# 28ChFNIRS.net
KiCad netlist of a schematic drawn in EAGLE
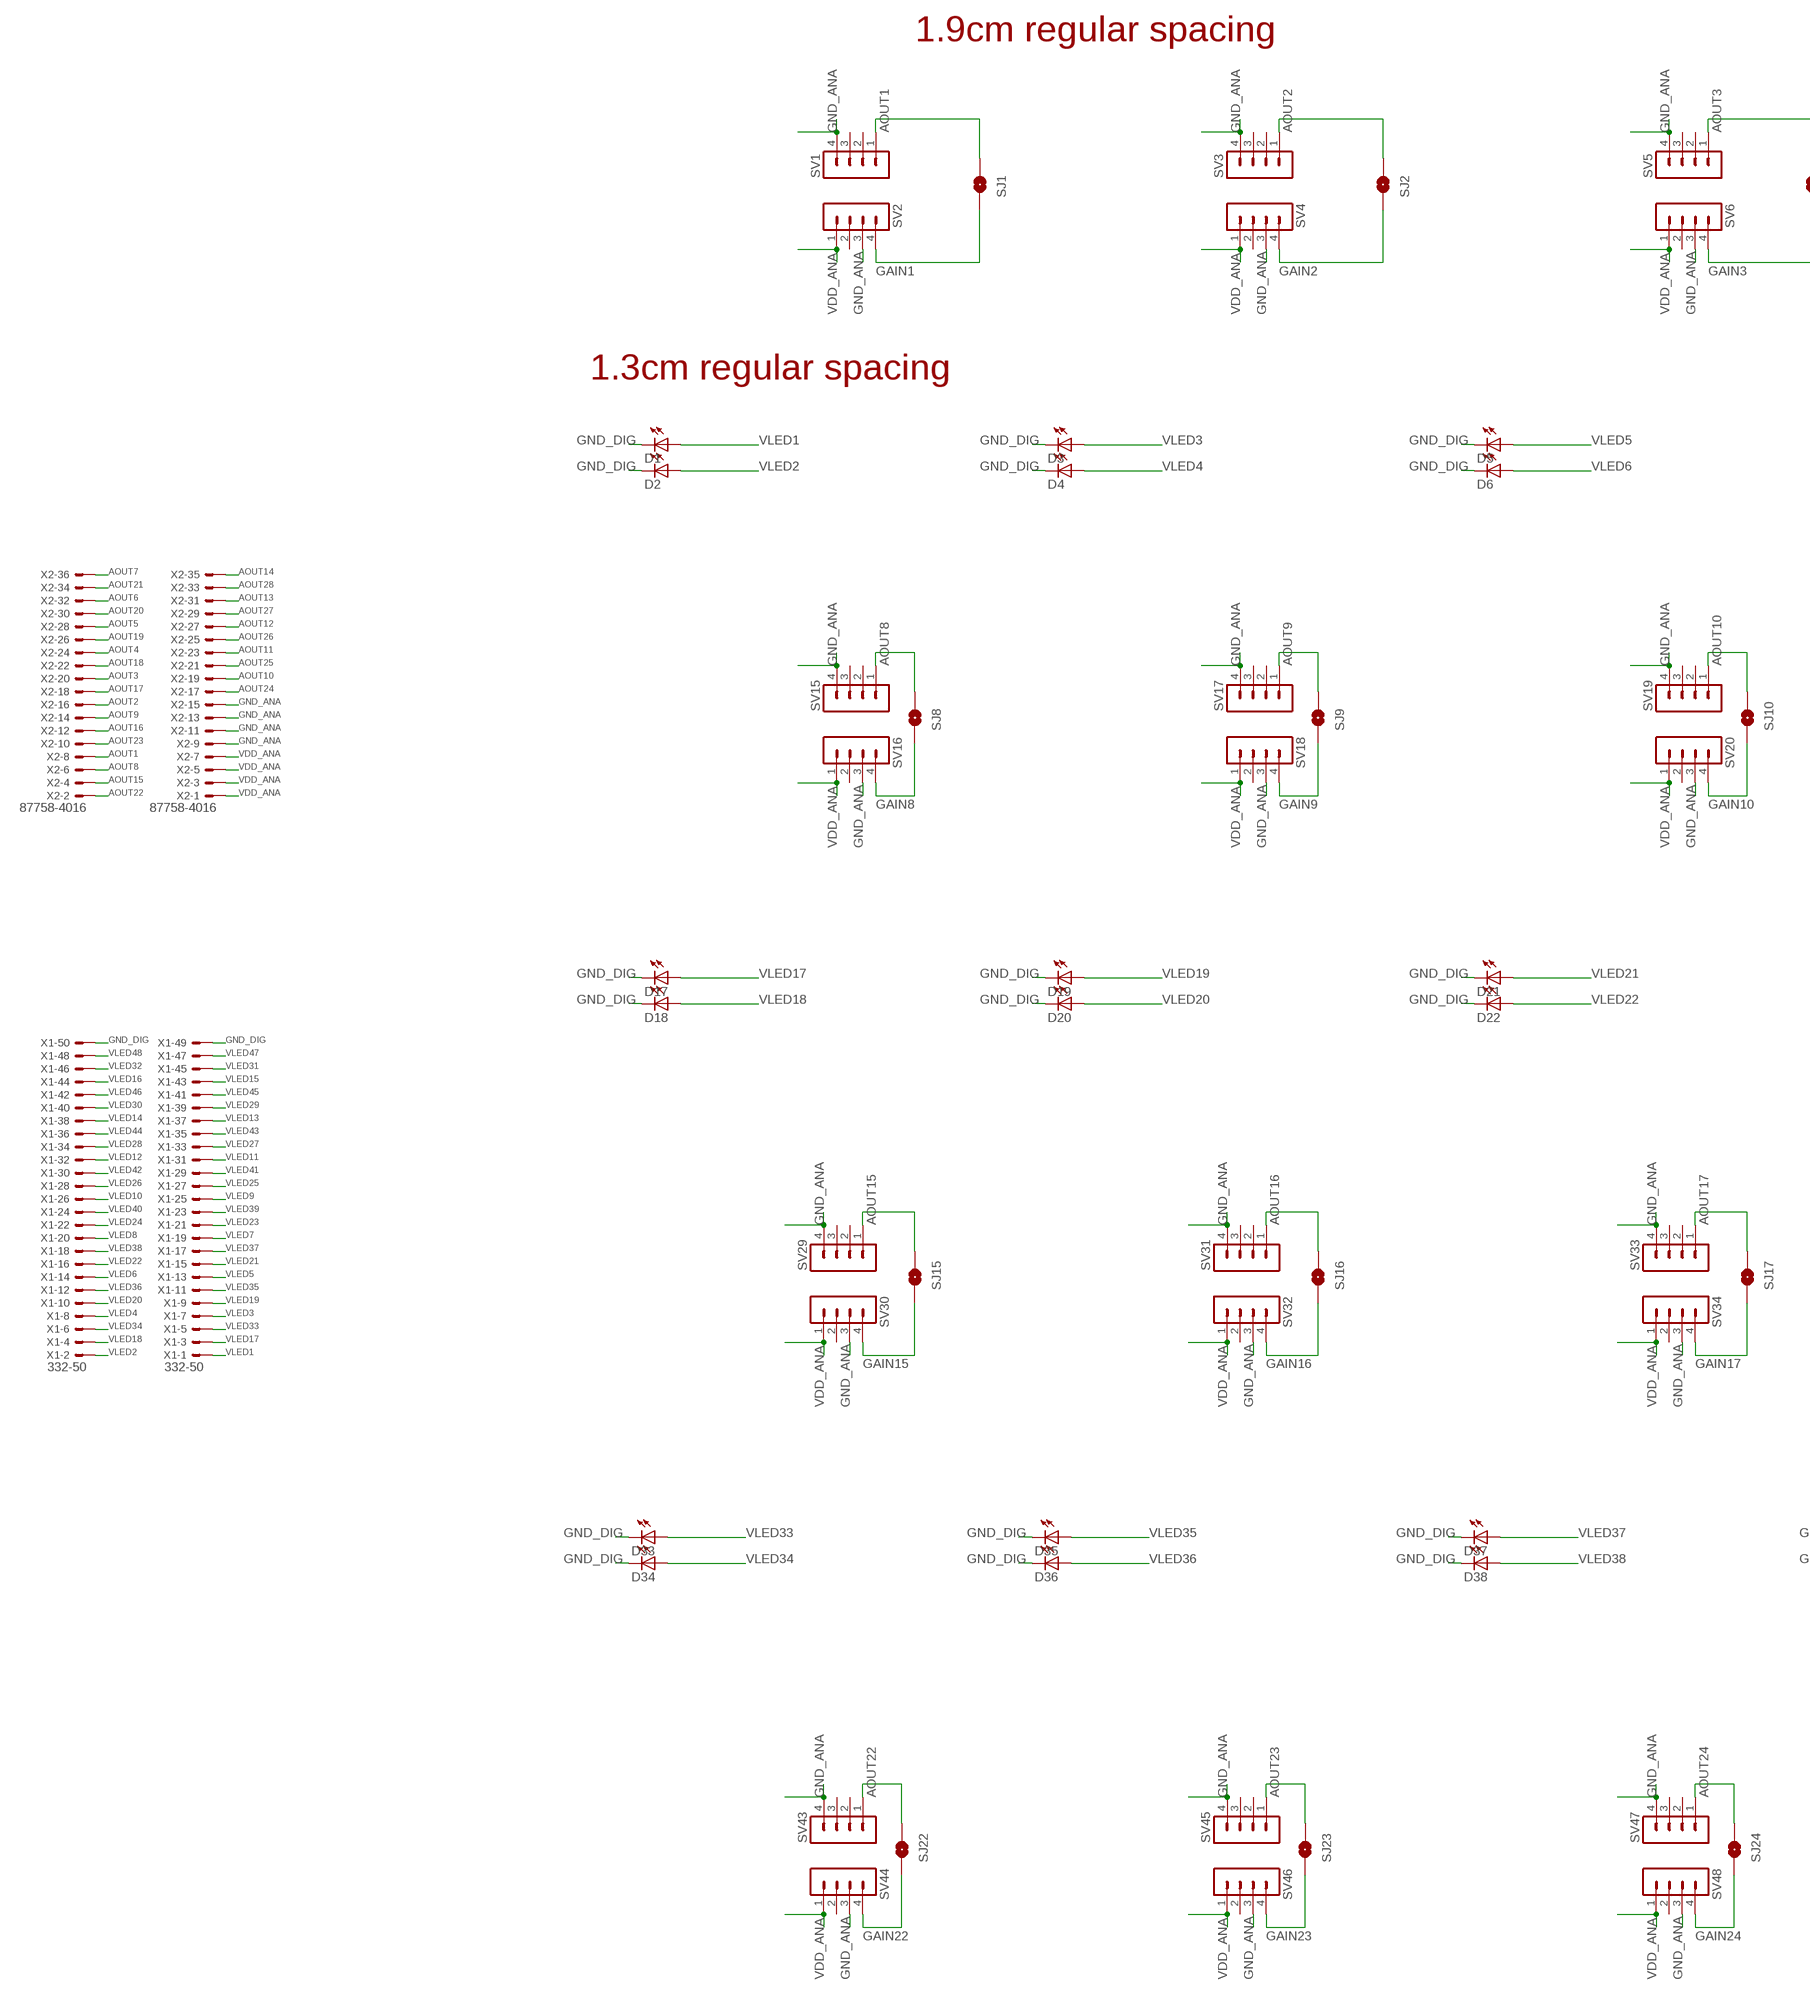
[diagram p0: schematic, sheet 1, part 1 of 2]
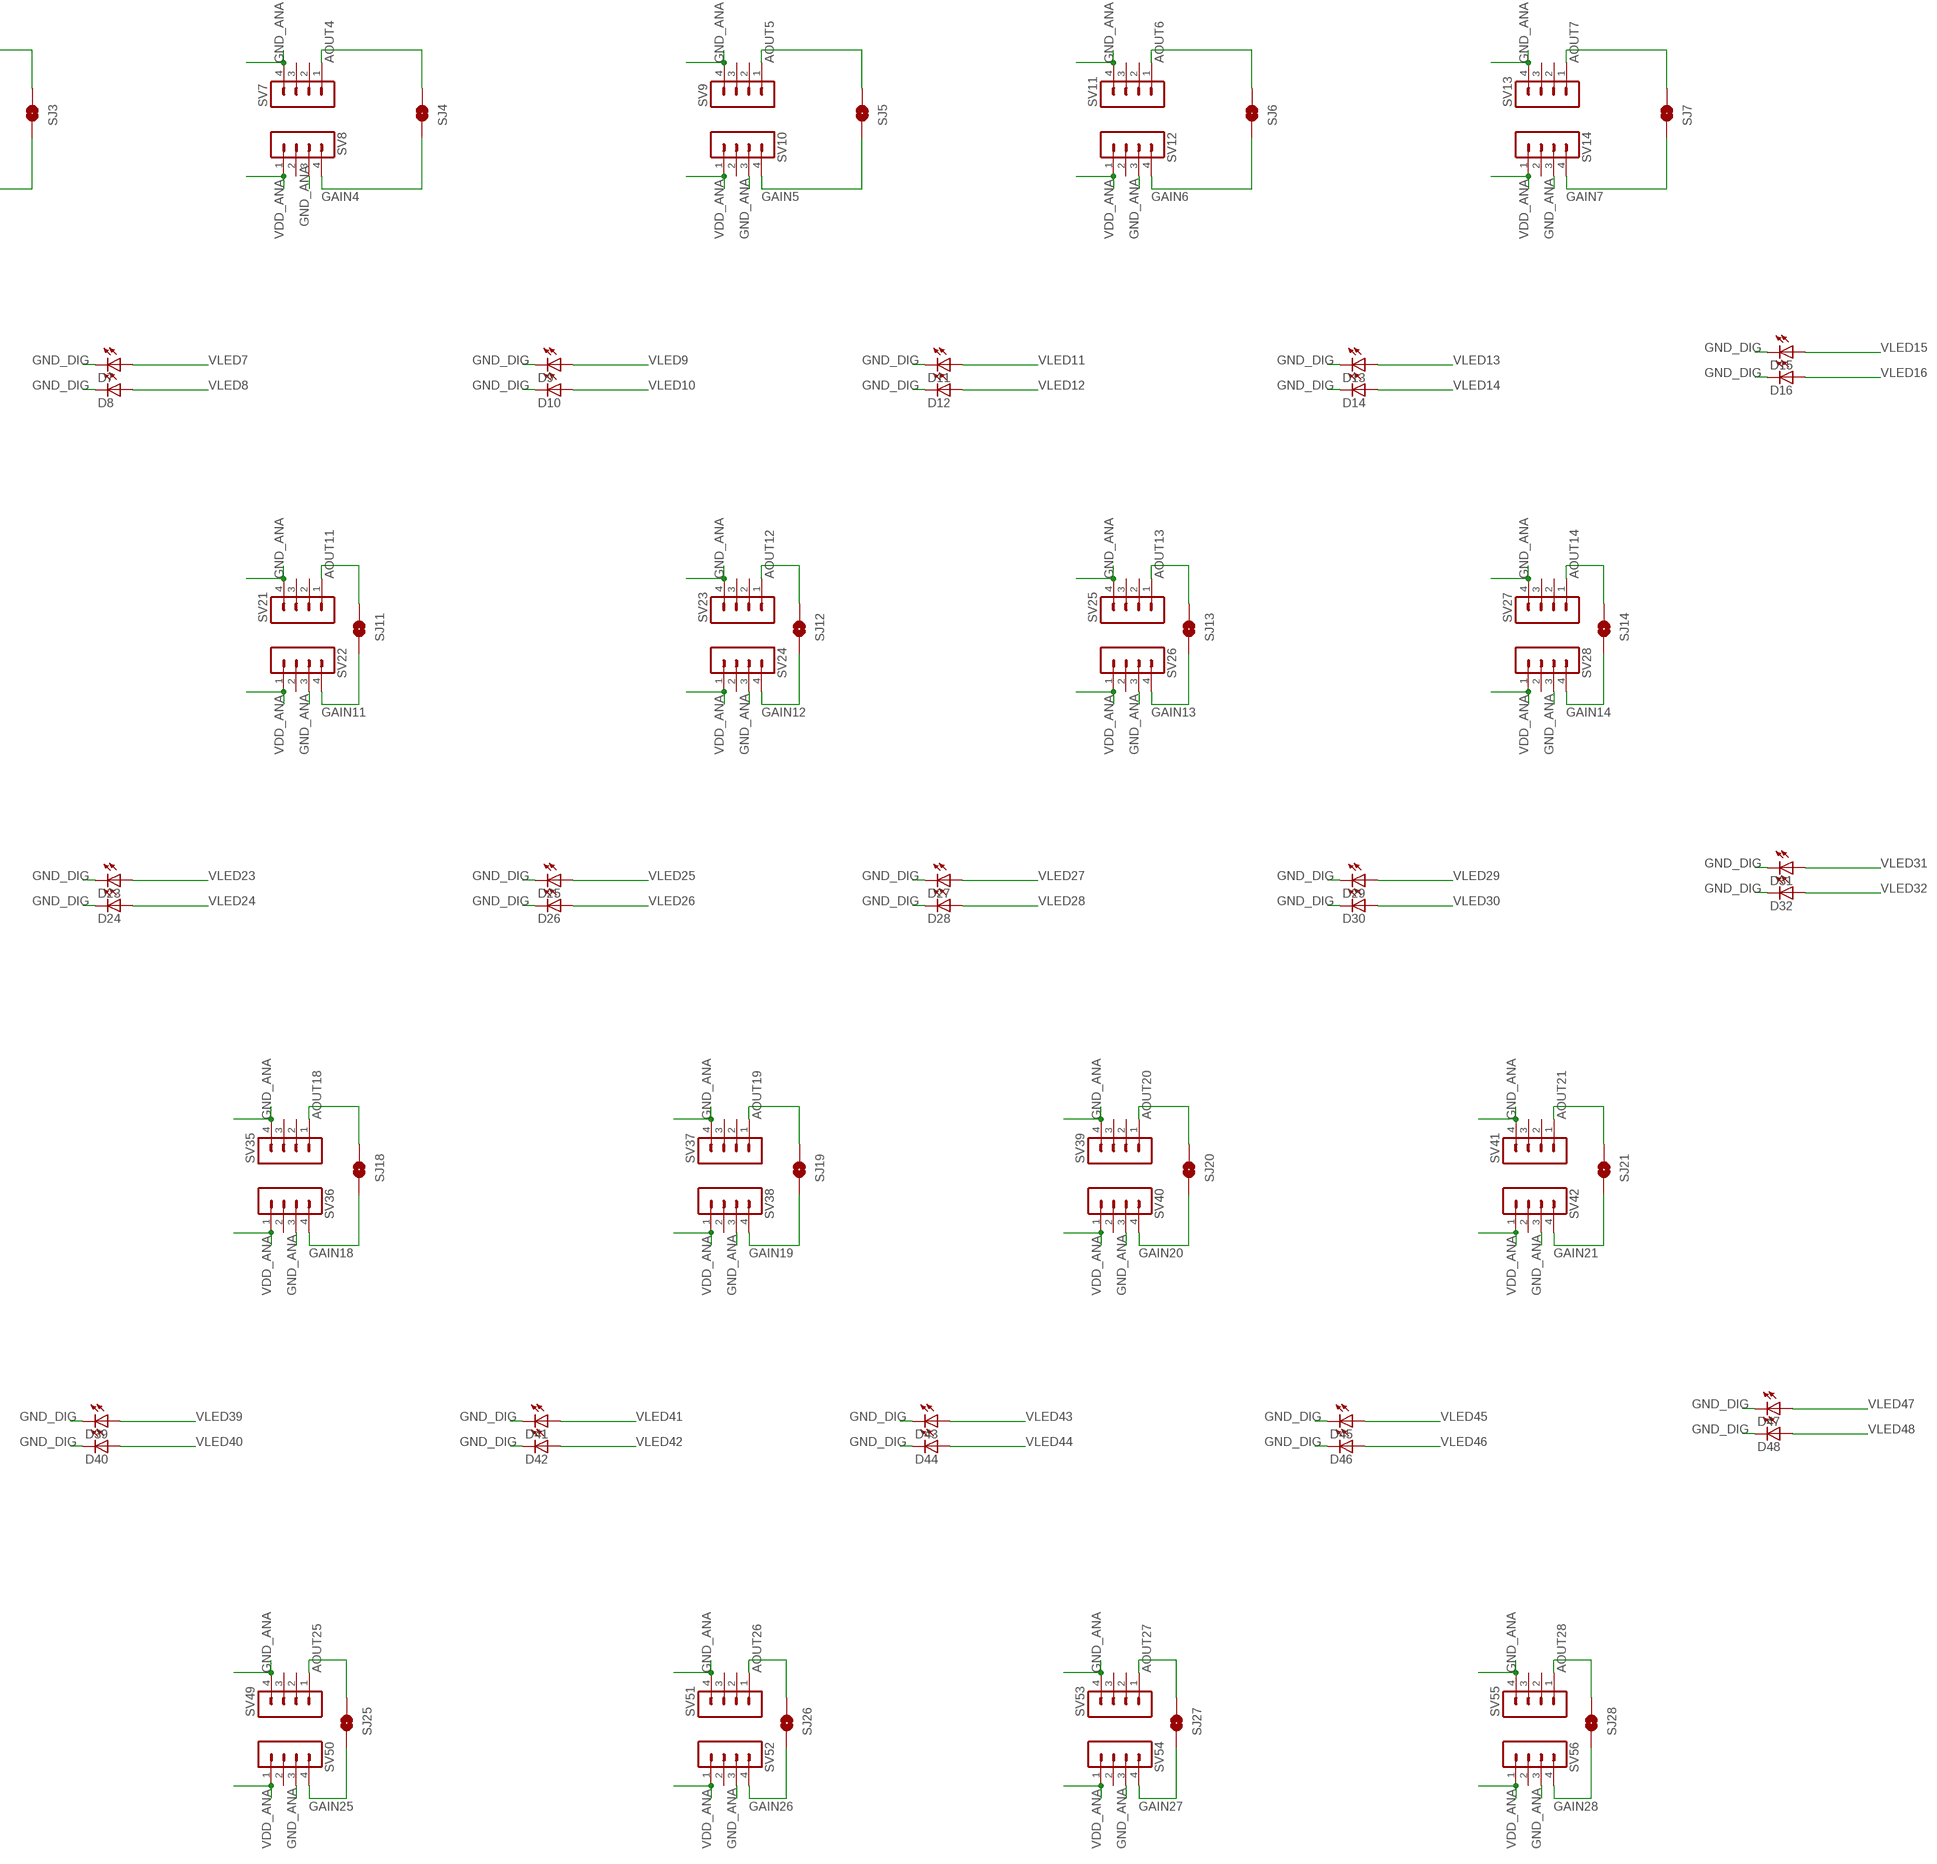
[diagram p1: schematic, sheet 1, part 2 of 2]

(export (version "E")
  (design (tool "Eeschema 10.0.6"))
  (components
    (comp (ref "D1")
      (value "LED1206")
      (footprint "eagle-import:LED-1206")
      (libsource (lib "eagle-import") (part "LED1206"))
    )
    (comp (ref "D2")
      (value "LED1206")
      (footprint "eagle-import:LED-1206")
      (libsource (lib "eagle-import") (part "LED1206"))
    )
    (comp (ref "D3")
      (value "LED1206")
      (footprint "eagle-import:LED-1206")
      (libsource (lib "eagle-import") (part "LED1206"))
    )
    (comp (ref "D4")
      (value "LED1206")
      (footprint "eagle-import:LED-1206")
      (libsource (lib "eagle-import") (part "LED1206"))
    )
    (comp (ref "D5")
      (value "LED1206")
      (footprint "eagle-import:LED-1206")
      (libsource (lib "eagle-import") (part "LED1206"))
    )
    (comp (ref "D6")
      (value "LED1206")
      (footprint "eagle-import:LED-1206")
      (libsource (lib "eagle-import") (part "LED1206"))
    )
    (comp (ref "D7")
      (value "LED1206")
      (footprint "eagle-import:LED-1206")
      (libsource (lib "eagle-import") (part "LED1206"))
    )
    (comp (ref "D8")
      (value "LED1206")
      (footprint "eagle-import:LED-1206")
      (libsource (lib "eagle-import") (part "LED1206"))
    )
    (comp (ref "D9")
      (value "LED1206")
      (footprint "eagle-import:LED-1206")
      (libsource (lib "eagle-import") (part "LED1206"))
    )
    (comp (ref "D10")
      (value "LED1206")
      (footprint "eagle-import:LED-1206")
      (libsource (lib "eagle-import") (part "LED1206"))
    )
    (comp (ref "D11")
      (value "LED1206")
      (footprint "eagle-import:LED-1206")
      (libsource (lib "eagle-import") (part "LED1206"))
    )
    (comp (ref "D12")
      (value "LED1206")
      (footprint "eagle-import:LED-1206")
      (libsource (lib "eagle-import") (part "LED1206"))
    )
    (comp (ref "D13")
      (value "LED1206")
      (footprint "eagle-import:LED-1206")
      (libsource (lib "eagle-import") (part "LED1206"))
    )
    (comp (ref "D14")
      (value "LED1206")
      (footprint "eagle-import:LED-1206")
      (libsource (lib "eagle-import") (part "LED1206"))
    )
    (comp (ref "D15")
      (value "LED1206")
      (footprint "eagle-import:LED-1206")
      (libsource (lib "eagle-import") (part "LED1206"))
    )
    (comp (ref "D16")
      (value "LED1206")
      (footprint "eagle-import:LED-1206")
      (libsource (lib "eagle-import") (part "LED1206"))
    )
    (comp (ref "D17")
      (value "LED1206")
      (footprint "eagle-import:LED-1206")
      (libsource (lib "eagle-import") (part "LED1206"))
    )
    (comp (ref "D18")
      (value "LED1206")
      (footprint "eagle-import:LED-1206")
      (libsource (lib "eagle-import") (part "LED1206"))
    )
    (comp (ref "D19")
      (value "LED1206")
      (footprint "eagle-import:LED-1206")
      (libsource (lib "eagle-import") (part "LED1206"))
    )
    (comp (ref "D20")
      (value "LED1206")
      (footprint "eagle-import:LED-1206")
      (libsource (lib "eagle-import") (part "LED1206"))
    )
    (comp (ref "D21")
      (value "LED1206")
      (footprint "eagle-import:LED-1206")
      (libsource (lib "eagle-import") (part "LED1206"))
    )
    (comp (ref "D22")
      (value "LED1206")
      (footprint "eagle-import:LED-1206")
      (libsource (lib "eagle-import") (part "LED1206"))
    )
    (comp (ref "D23")
      (value "LED1206")
      (footprint "eagle-import:LED-1206")
      (libsource (lib "eagle-import") (part "LED1206"))
    )
    (comp (ref "D24")
      (value "LED1206")
      (footprint "eagle-import:LED-1206")
      (libsource (lib "eagle-import") (part "LED1206"))
    )
    (comp (ref "D25")
      (value "LED1206")
      (footprint "eagle-import:LED-1206")
      (libsource (lib "eagle-import") (part "LED1206"))
    )
    (comp (ref "D26")
      (value "LED1206")
      (footprint "eagle-import:LED-1206")
      (libsource (lib "eagle-import") (part "LED1206"))
    )
    (comp (ref "D27")
      (value "LED1206")
      (footprint "eagle-import:LED-1206")
      (libsource (lib "eagle-import") (part "LED1206"))
    )
    (comp (ref "D28")
      (value "LED1206")
      (footprint "eagle-import:LED-1206")
      (libsource (lib "eagle-import") (part "LED1206"))
    )
    (comp (ref "D29")
      (value "LED1206")
      (footprint "eagle-import:LED-1206")
      (libsource (lib "eagle-import") (part "LED1206"))
    )
    (comp (ref "D30")
      (value "LED1206")
      (footprint "eagle-import:LED-1206")
      (libsource (lib "eagle-import") (part "LED1206"))
    )
    (comp (ref "D31")
      (value "LED1206")
      (footprint "eagle-import:LED-1206")
      (libsource (lib "eagle-import") (part "LED1206"))
    )
    (comp (ref "D32")
      (value "LED1206")
      (footprint "eagle-import:LED-1206")
      (libsource (lib "eagle-import") (part "LED1206"))
    )
    (comp (ref "D33")
      (value "LED1206")
      (footprint "eagle-import:LED-1206")
      (libsource (lib "eagle-import") (part "LED1206"))
    )
    (comp (ref "D34")
      (value "LED1206")
      (footprint "eagle-import:LED-1206")
      (libsource (lib "eagle-import") (part "LED1206"))
    )
    (comp (ref "D35")
      (value "LED1206")
      (footprint "eagle-import:LED-1206")
      (libsource (lib "eagle-import") (part "LED1206"))
    )
    (comp (ref "D36")
      (value "LED1206")
      (footprint "eagle-import:LED-1206")
      (libsource (lib "eagle-import") (part "LED1206"))
    )
    (comp (ref "D37")
      (value "LED1206")
      (footprint "eagle-import:LED-1206")
      (libsource (lib "eagle-import") (part "LED1206"))
    )
    (comp (ref "D38")
      (value "LED1206")
      (footprint "eagle-import:LED-1206")
      (libsource (lib "eagle-import") (part "LED1206"))
    )
    (comp (ref "D39")
      (value "LED1206")
      (footprint "eagle-import:LED-1206")
      (libsource (lib "eagle-import") (part "LED1206"))
    )
    (comp (ref "D40")
      (value "LED1206")
      (footprint "eagle-import:LED-1206")
      (libsource (lib "eagle-import") (part "LED1206"))
    )
    (comp (ref "D41")
      (value "LED1206")
      (footprint "eagle-import:LED-1206")
      (libsource (lib "eagle-import") (part "LED1206"))
    )
    (comp (ref "D42")
      (value "LED1206")
      (footprint "eagle-import:LED-1206")
      (libsource (lib "eagle-import") (part "LED1206"))
    )
    (comp (ref "D43")
      (value "LED1206")
      (footprint "eagle-import:LED-1206")
      (libsource (lib "eagle-import") (part "LED1206"))
    )
    (comp (ref "D44")
      (value "LED1206")
      (footprint "eagle-import:LED-1206")
      (libsource (lib "eagle-import") (part "LED1206"))
    )
    (comp (ref "D45")
      (value "LED1206")
      (footprint "eagle-import:LED-1206")
      (libsource (lib "eagle-import") (part "LED1206"))
    )
    (comp (ref "D46")
      (value "LED1206")
      (footprint "eagle-import:LED-1206")
      (libsource (lib "eagle-import") (part "LED1206"))
    )
    (comp (ref "D47")
      (value "LED1206")
      (footprint "eagle-import:LED-1206")
      (libsource (lib "eagle-import") (part "LED1206"))
    )
    (comp (ref "D48")
      (value "LED1206")
      (footprint "eagle-import:LED-1206")
      (libsource (lib "eagle-import") (part "LED1206"))
    )
    (comp (ref "SJ1")
      (value "SOLDERJUMPERNC")
      (footprint "eagle-import:SJ_2S_SMALL")
      (libsource (lib "eagle-import") (part "SOLDERJUMPERNC"))
    )
    (comp (ref "SJ2")
      (value "SOLDERJUMPERNC")
      (footprint "eagle-import:SJ_2S_SMALL")
      (libsource (lib "eagle-import") (part "SOLDERJUMPERNC"))
    )
    (comp (ref "SJ3")
      (value "SOLDERJUMPERNC")
      (footprint "eagle-import:SJ_2S_SMALL")
      (libsource (lib "eagle-import") (part "SOLDERJUMPERNC"))
    )
    (comp (ref "SJ4")
      (value "SOLDERJUMPERNC")
      (footprint "eagle-import:SJ_2S_SMALL")
      (libsource (lib "eagle-import") (part "SOLDERJUMPERNC"))
    )
    (comp (ref "SJ5")
      (value "SOLDERJUMPERNC")
      (footprint "eagle-import:SJ_2S_SMALL")
      (libsource (lib "eagle-import") (part "SOLDERJUMPERNC"))
    )
    (comp (ref "SJ6")
      (value "SOLDERJUMPERNC")
      (footprint "eagle-import:SJ_2S_SMALL")
      (libsource (lib "eagle-import") (part "SOLDERJUMPERNC"))
    )
    (comp (ref "SJ7")
      (value "SOLDERJUMPERNC")
      (footprint "eagle-import:SJ_2S_SMALL")
      (libsource (lib "eagle-import") (part "SOLDERJUMPERNC"))
    )
    (comp (ref "SJ8")
      (value "SOLDERJUMPERNC")
      (footprint "eagle-import:SJ_2S_SMALL")
      (libsource (lib "eagle-import") (part "SOLDERJUMPERNC"))
    )
    (comp (ref "SJ9")
      (value "SOLDERJUMPERNC")
      (footprint "eagle-import:SJ_2S_SMALL")
      (libsource (lib "eagle-import") (part "SOLDERJUMPERNC"))
    )
    (comp (ref "SJ10")
      (value "SOLDERJUMPERNC")
      (footprint "eagle-import:SJ_2S_SMALL")
      (libsource (lib "eagle-import") (part "SOLDERJUMPERNC"))
    )
    (comp (ref "SJ11")
      (value "SOLDERJUMPERNC")
      (footprint "eagle-import:SJ_2S_SMALL")
      (libsource (lib "eagle-import") (part "SOLDERJUMPERNC"))
    )
    (comp (ref "SJ12")
      (value "SOLDERJUMPERNC")
      (footprint "eagle-import:SJ_2S_SMALL")
      (libsource (lib "eagle-import") (part "SOLDERJUMPERNC"))
    )
    (comp (ref "SJ13")
      (value "SOLDERJUMPERNC")
      (footprint "eagle-import:SJ_2S_SMALL")
      (libsource (lib "eagle-import") (part "SOLDERJUMPERNC"))
    )
    (comp (ref "SJ14")
      (value "SOLDERJUMPERNC")
      (footprint "eagle-import:SJ_2S_SMALL")
      (libsource (lib "eagle-import") (part "SOLDERJUMPERNC"))
    )
    (comp (ref "SJ15")
      (value "SOLDERJUMPERNC")
      (footprint "eagle-import:SJ_2S_SMALL")
      (libsource (lib "eagle-import") (part "SOLDERJUMPERNC"))
    )
    (comp (ref "SJ16")
      (value "SOLDERJUMPERNC")
      (footprint "eagle-import:SJ_2S_SMALL")
      (libsource (lib "eagle-import") (part "SOLDERJUMPERNC"))
    )
    (comp (ref "SJ17")
      (value "SOLDERJUMPERNC")
      (footprint "eagle-import:SJ_2S_SMALL")
      (libsource (lib "eagle-import") (part "SOLDERJUMPERNC"))
    )
    (comp (ref "SJ18")
      (value "SOLDERJUMPERNC")
      (footprint "eagle-import:SJ_2S_SMALL")
      (libsource (lib "eagle-import") (part "SOLDERJUMPERNC"))
    )
    (comp (ref "SJ19")
      (value "SOLDERJUMPERNC")
      (footprint "eagle-import:SJ_2S_SMALL")
      (libsource (lib "eagle-import") (part "SOLDERJUMPERNC"))
    )
    (comp (ref "SJ20")
      (value "SOLDERJUMPERNC")
      (footprint "eagle-import:SJ_2S_SMALL")
      (libsource (lib "eagle-import") (part "SOLDERJUMPERNC"))
    )
    (comp (ref "SJ21")
      (value "SOLDERJUMPERNC")
      (footprint "eagle-import:SJ_2S_SMALL")
      (libsource (lib "eagle-import") (part "SOLDERJUMPERNC"))
    )
    (comp (ref "SJ22")
      (value "SOLDERJUMPERNC")
      (footprint "eagle-import:SJ_2S_SMALL")
      (libsource (lib "eagle-import") (part "SOLDERJUMPERNC"))
    )
    (comp (ref "SJ23")
      (value "SOLDERJUMPERNC")
      (footprint "eagle-import:SJ_2S_SMALL")
      (libsource (lib "eagle-import") (part "SOLDERJUMPERNC"))
    )
    (comp (ref "SJ24")
      (value "SOLDERJUMPERNC")
      (footprint "eagle-import:SJ_2S_SMALL")
      (libsource (lib "eagle-import") (part "SOLDERJUMPERNC"))
    )
    (comp (ref "SJ25")
      (value "SOLDERJUMPERNC")
      (footprint "eagle-import:SJ_2S_SMALL")
      (libsource (lib "eagle-import") (part "SOLDERJUMPERNC"))
    )
    (comp (ref "SJ26")
      (value "SOLDERJUMPERNC")
      (footprint "eagle-import:SJ_2S_SMALL")
      (libsource (lib "eagle-import") (part "SOLDERJUMPERNC"))
    )
    (comp (ref "SJ27")
      (value "SOLDERJUMPERNC")
      (footprint "eagle-import:SJ_2S_SMALL")
      (libsource (lib "eagle-import") (part "SOLDERJUMPERNC"))
    )
    (comp (ref "SJ28")
      (value "SOLDERJUMPERNC")
      (footprint "eagle-import:SJ_2S_SMALL")
      (libsource (lib "eagle-import") (part "SOLDERJUMPERNC"))
    )
    (comp (ref "SV1")
      (value "MA04-1")
      (footprint "eagle-import:MA04-1")
      (libsource (lib "eagle-import") (part "MA04-1"))
    )
    (comp (ref "SV2")
      (value "MA04-1")
      (footprint "eagle-import:MA04-1")
      (libsource (lib "eagle-import") (part "MA04-1"))
    )
    (comp (ref "SV3")
      (value "MA04-1")
      (footprint "eagle-import:MA04-1")
      (libsource (lib "eagle-import") (part "MA04-1"))
    )
    (comp (ref "SV4")
      (value "MA04-1")
      (footprint "eagle-import:MA04-1")
      (libsource (lib "eagle-import") (part "MA04-1"))
    )
    (comp (ref "SV5")
      (value "MA04-1")
      (footprint "eagle-import:MA04-1")
      (libsource (lib "eagle-import") (part "MA04-1"))
    )
    (comp (ref "SV6")
      (value "MA04-1")
      (footprint "eagle-import:MA04-1")
      (libsource (lib "eagle-import") (part "MA04-1"))
    )
    (comp (ref "SV7")
      (value "MA04-1")
      (footprint "eagle-import:MA04-1")
      (libsource (lib "eagle-import") (part "MA04-1"))
    )
    (comp (ref "SV8")
      (value "MA04-1")
      (footprint "eagle-import:MA04-1")
      (libsource (lib "eagle-import") (part "MA04-1"))
    )
    (comp (ref "SV9")
      (value "MA04-1")
      (footprint "eagle-import:MA04-1")
      (libsource (lib "eagle-import") (part "MA04-1"))
    )
    (comp (ref "SV10")
      (value "MA04-1")
      (footprint "eagle-import:MA04-1")
      (libsource (lib "eagle-import") (part "MA04-1"))
    )
    (comp (ref "SV11")
      (value "MA04-1")
      (footprint "eagle-import:MA04-1")
      (libsource (lib "eagle-import") (part "MA04-1"))
    )
    (comp (ref "SV12")
      (value "MA04-1")
      (footprint "eagle-import:MA04-1")
      (libsource (lib "eagle-import") (part "MA04-1"))
    )
    (comp (ref "SV13")
      (value "MA04-1")
      (footprint "eagle-import:MA04-1")
      (libsource (lib "eagle-import") (part "MA04-1"))
    )
    (comp (ref "SV14")
      (value "MA04-1")
      (footprint "eagle-import:MA04-1")
      (libsource (lib "eagle-import") (part "MA04-1"))
    )
    (comp (ref "SV15")
      (value "MA04-1")
      (footprint "eagle-import:MA04-1")
      (libsource (lib "eagle-import") (part "MA04-1"))
    )
    (comp (ref "SV16")
      (value "MA04-1")
      (footprint "eagle-import:MA04-1")
      (libsource (lib "eagle-import") (part "MA04-1"))
    )
    (comp (ref "SV17")
      (value "MA04-1")
      (footprint "eagle-import:MA04-1")
      (libsource (lib "eagle-import") (part "MA04-1"))
    )
    (comp (ref "SV18")
      (value "MA04-1")
      (footprint "eagle-import:MA04-1")
      (libsource (lib "eagle-import") (part "MA04-1"))
    )
    (comp (ref "SV19")
      (value "MA04-1")
      (footprint "eagle-import:MA04-1")
      (libsource (lib "eagle-import") (part "MA04-1"))
    )
    (comp (ref "SV20")
      (value "MA04-1")
      (footprint "eagle-import:MA04-1")
      (libsource (lib "eagle-import") (part "MA04-1"))
    )
    (comp (ref "SV21")
      (value "MA04-1")
      (footprint "eagle-import:MA04-1")
      (libsource (lib "eagle-import") (part "MA04-1"))
    )
    (comp (ref "SV22")
      (value "MA04-1")
      (footprint "eagle-import:MA04-1")
      (libsource (lib "eagle-import") (part "MA04-1"))
    )
    (comp (ref "SV23")
      (value "MA04-1")
      (footprint "eagle-import:MA04-1")
      (libsource (lib "eagle-import") (part "MA04-1"))
    )
    (comp (ref "SV24")
      (value "MA04-1")
      (footprint "eagle-import:MA04-1")
      (libsource (lib "eagle-import") (part "MA04-1"))
    )
    (comp (ref "SV25")
      (value "MA04-1")
      (footprint "eagle-import:MA04-1")
      (libsource (lib "eagle-import") (part "MA04-1"))
    )
    (comp (ref "SV26")
      (value "MA04-1")
      (footprint "eagle-import:MA04-1")
      (libsource (lib "eagle-import") (part "MA04-1"))
    )
    (comp (ref "SV27")
      (value "MA04-1")
      (footprint "eagle-import:MA04-1")
      (libsource (lib "eagle-import") (part "MA04-1"))
    )
    (comp (ref "SV28")
      (value "MA04-1")
      (footprint "eagle-import:MA04-1")
      (libsource (lib "eagle-import") (part "MA04-1"))
    )
    (comp (ref "SV29")
      (value "MA04-1")
      (footprint "eagle-import:MA04-1")
      (libsource (lib "eagle-import") (part "MA04-1"))
    )
    (comp (ref "SV30")
      (value "MA04-1")
      (footprint "eagle-import:MA04-1")
      (libsource (lib "eagle-import") (part "MA04-1"))
    )
    (comp (ref "SV31")
      (value "MA04-1")
      (footprint "eagle-import:MA04-1")
      (libsource (lib "eagle-import") (part "MA04-1"))
    )
    (comp (ref "SV32")
      (value "MA04-1")
      (footprint "eagle-import:MA04-1")
      (libsource (lib "eagle-import") (part "MA04-1"))
    )
    (comp (ref "SV33")
      (value "MA04-1")
      (footprint "eagle-import:MA04-1")
      (libsource (lib "eagle-import") (part "MA04-1"))
    )
    (comp (ref "SV34")
      (value "MA04-1")
      (footprint "eagle-import:MA04-1")
      (libsource (lib "eagle-import") (part "MA04-1"))
    )
    (comp (ref "SV35")
      (value "MA04-1")
      (footprint "eagle-import:MA04-1")
      (libsource (lib "eagle-import") (part "MA04-1"))
    )
    (comp (ref "SV36")
      (value "MA04-1")
      (footprint "eagle-import:MA04-1")
      (libsource (lib "eagle-import") (part "MA04-1"))
    )
    (comp (ref "SV37")
      (value "MA04-1")
      (footprint "eagle-import:MA04-1")
      (libsource (lib "eagle-import") (part "MA04-1"))
    )
    (comp (ref "SV38")
      (value "MA04-1")
      (footprint "eagle-import:MA04-1")
      (libsource (lib "eagle-import") (part "MA04-1"))
    )
    (comp (ref "SV39")
      (value "MA04-1")
      (footprint "eagle-import:MA04-1")
      (libsource (lib "eagle-import") (part "MA04-1"))
    )
    (comp (ref "SV40")
      (value "MA04-1")
      (footprint "eagle-import:MA04-1")
      (libsource (lib "eagle-import") (part "MA04-1"))
    )
    (comp (ref "SV41")
      (value "MA04-1")
      (footprint "eagle-import:MA04-1")
      (libsource (lib "eagle-import") (part "MA04-1"))
    )
    (comp (ref "SV42")
      (value "MA04-1")
      (footprint "eagle-import:MA04-1")
      (libsource (lib "eagle-import") (part "MA04-1"))
    )
    (comp (ref "SV43")
      (value "MA04-1")
      (footprint "eagle-import:MA04-1")
      (libsource (lib "eagle-import") (part "MA04-1"))
    )
    (comp (ref "SV44")
      (value "MA04-1")
      (footprint "eagle-import:MA04-1")
      (libsource (lib "eagle-import") (part "MA04-1"))
    )
    (comp (ref "SV45")
      (value "MA04-1")
      (footprint "eagle-import:MA04-1")
      (libsource (lib "eagle-import") (part "MA04-1"))
    )
    (comp (ref "SV46")
      (value "MA04-1")
      (footprint "eagle-import:MA04-1")
      (libsource (lib "eagle-import") (part "MA04-1"))
    )
    (comp (ref "SV47")
      (value "MA04-1")
      (footprint "eagle-import:MA04-1")
      (libsource (lib "eagle-import") (part "MA04-1"))
    )
    (comp (ref "SV48")
      (value "MA04-1")
      (footprint "eagle-import:MA04-1")
      (libsource (lib "eagle-import") (part "MA04-1"))
    )
    (comp (ref "SV49")
      (value "MA04-1")
      (footprint "eagle-import:MA04-1")
      (libsource (lib "eagle-import") (part "MA04-1"))
    )
    (comp (ref "SV50")
      (value "MA04-1")
      (footprint "eagle-import:MA04-1")
      (libsource (lib "eagle-import") (part "MA04-1"))
    )
    (comp (ref "SV51")
      (value "MA04-1")
      (footprint "eagle-import:MA04-1")
      (libsource (lib "eagle-import") (part "MA04-1"))
    )
    (comp (ref "SV52")
      (value "MA04-1")
      (footprint "eagle-import:MA04-1")
      (libsource (lib "eagle-import") (part "MA04-1"))
    )
    (comp (ref "SV53")
      (value "MA04-1")
      (footprint "eagle-import:MA04-1")
      (libsource (lib "eagle-import") (part "MA04-1"))
    )
    (comp (ref "SV54")
      (value "MA04-1")
      (footprint "eagle-import:MA04-1")
      (libsource (lib "eagle-import") (part "MA04-1"))
    )
    (comp (ref "SV55")
      (value "MA04-1")
      (footprint "eagle-import:MA04-1")
      (libsource (lib "eagle-import") (part "MA04-1"))
    )
    (comp (ref "SV56")
      (value "MA04-1")
      (footprint "eagle-import:MA04-1")
      (libsource (lib "eagle-import") (part "MA04-1"))
    )
    (comp (ref "X1")
      (value "332-50")
      (footprint "eagle-import:332-50")
      (libsource (lib "eagle-import") (part "332-50"))
    )
    (comp (ref "X2")
      (value "87758-4016")
      (footprint "eagle-import:87758-4016")
      (fields (field (name "MF") "MOLEX"))
      (libsource (lib "eagle-import") (part "87758-4016"))
    )
  )
  (nets
    (net (code "1") (name "/AOUT1") (class "Default")
      (node (ref "SJ1") (pin "2") (pinfunction "2_2") (pintype "passive"))
      (node (ref "SV1") (pin "1") (pinfunction "1_1") (pintype "passive"))
      (node (ref "X2") (pin "8") (pinfunction "S_8") (pintype "passive"))
    )
    (net (code "2") (name "/AOUT2") (class "Default")
      (node (ref "SJ2") (pin "2") (pinfunction "2_2") (pintype "passive"))
      (node (ref "SV3") (pin "1") (pinfunction "1_1") (pintype "passive"))
      (node (ref "X2") (pin "16") (pinfunction "S_16") (pintype "passive"))
    )
    (net (code "3") (name "/AOUT3") (class "Default")
      (node (ref "SJ3") (pin "2") (pinfunction "2_2") (pintype "passive"))
      (node (ref "SV5") (pin "1") (pinfunction "1_1") (pintype "passive"))
      (node (ref "X2") (pin "20") (pinfunction "S_20") (pintype "passive"))
    )
    (net (code "4") (name "/AOUT4") (class "Default")
      (node (ref "SJ4") (pin "2") (pinfunction "2_2") (pintype "passive"))
      (node (ref "SV7") (pin "1") (pinfunction "1_1") (pintype "passive"))
      (node (ref "X2") (pin "24") (pinfunction "S_24") (pintype "passive"))
    )
    (net (code "5") (name "/AOUT5") (class "Default")
      (node (ref "SJ5") (pin "2") (pinfunction "2_2") (pintype "passive"))
      (node (ref "SV9") (pin "1") (pinfunction "1_1") (pintype "passive"))
      (node (ref "X2") (pin "28") (pinfunction "S_28") (pintype "passive"))
    )
    (net (code "6") (name "/AOUT6") (class "Default")
      (node (ref "SJ6") (pin "2") (pinfunction "2_2") (pintype "passive"))
      (node (ref "SV11") (pin "1") (pinfunction "1_1") (pintype "passive"))
      (node (ref "X2") (pin "32") (pinfunction "S_32") (pintype "passive"))
    )
    (net (code "7") (name "/AOUT7") (class "Default")
      (node (ref "SJ7") (pin "2") (pinfunction "2_2") (pintype "passive"))
      (node (ref "SV13") (pin "1") (pinfunction "1_1") (pintype "passive"))
      (node (ref "X2") (pin "36") (pinfunction "S_36") (pintype "passive"))
    )
    (net (code "8") (name "/AOUT8") (class "Default")
      (node (ref "SJ8") (pin "2") (pinfunction "2_2") (pintype "passive"))
      (node (ref "SV15") (pin "1") (pinfunction "1_1") (pintype "passive"))
      (node (ref "X2") (pin "6") (pinfunction "S_6") (pintype "passive"))
    )
    (net (code "9") (name "/AOUT9") (class "Default")
      (node (ref "SJ9") (pin "2") (pinfunction "2_2") (pintype "passive"))
      (node (ref "SV17") (pin "1") (pinfunction "1_1") (pintype "passive"))
      (node (ref "X2") (pin "14") (pinfunction "S_14") (pintype "passive"))
    )
    (net (code "10") (name "/AOUT10") (class "Default")
      (node (ref "SJ10") (pin "2") (pinfunction "2_2") (pintype "passive"))
      (node (ref "SV19") (pin "1") (pinfunction "1_1") (pintype "passive"))
      (node (ref "X2") (pin "19") (pinfunction "S_19") (pintype "passive"))
    )
    (net (code "11") (name "/AOUT11") (class "Default")
      (node (ref "SJ11") (pin "2") (pinfunction "2_2") (pintype "passive"))
      (node (ref "SV21") (pin "1") (pinfunction "1_1") (pintype "passive"))
      (node (ref "X2") (pin "23") (pinfunction "S_23") (pintype "passive"))
    )
    (net (code "12") (name "/AOUT12") (class "Default")
      (node (ref "SJ12") (pin "2") (pinfunction "2_2") (pintype "passive"))
      (node (ref "SV23") (pin "1") (pinfunction "1_1") (pintype "passive"))
      (node (ref "X2") (pin "27") (pinfunction "S_27") (pintype "passive"))
    )
    (net (code "13") (name "/AOUT13") (class "Default")
      (node (ref "SJ13") (pin "2") (pinfunction "2_2") (pintype "passive"))
      (node (ref "SV25") (pin "1") (pinfunction "1_1") (pintype "passive"))
      (node (ref "X2") (pin "31") (pinfunction "S_31") (pintype "passive"))
    )
    (net (code "14") (name "/AOUT14") (class "Default")
      (node (ref "SJ14") (pin "2") (pinfunction "2_2") (pintype "passive"))
      (node (ref "SV27") (pin "1") (pinfunction "1_1") (pintype "passive"))
      (node (ref "X2") (pin "35") (pinfunction "S_35") (pintype "passive"))
    )
    (net (code "15") (name "/AOUT15") (class "Default")
      (node (ref "SJ15") (pin "2") (pinfunction "2_2") (pintype "passive"))
      (node (ref "SV29") (pin "1") (pinfunction "1_1") (pintype "passive"))
      (node (ref "X2") (pin "4") (pinfunction "S_4") (pintype "passive"))
    )
    (net (code "16") (name "/AOUT16") (class "Default")
      (node (ref "SJ16") (pin "2") (pinfunction "2_2") (pintype "passive"))
      (node (ref "SV31") (pin "1") (pinfunction "1_1") (pintype "passive"))
      (node (ref "X2") (pin "12") (pinfunction "S_12") (pintype "passive"))
    )
    (net (code "17") (name "/AOUT17") (class "Default")
      (node (ref "SJ17") (pin "2") (pinfunction "2_2") (pintype "passive"))
      (node (ref "SV33") (pin "1") (pinfunction "1_1") (pintype "passive"))
      (node (ref "X2") (pin "18") (pinfunction "S_18") (pintype "passive"))
    )
    (net (code "18") (name "/AOUT18") (class "Default")
      (node (ref "SJ18") (pin "2") (pinfunction "2_2") (pintype "passive"))
      (node (ref "SV35") (pin "1") (pinfunction "1_1") (pintype "passive"))
      (node (ref "X2") (pin "22") (pinfunction "S_22") (pintype "passive"))
    )
    (net (code "19") (name "/AOUT19") (class "Default")
      (node (ref "SJ19") (pin "2") (pinfunction "2_2") (pintype "passive"))
      (node (ref "SV37") (pin "1") (pinfunction "1_1") (pintype "passive"))
      (node (ref "X2") (pin "26") (pinfunction "S_26") (pintype "passive"))
    )
    (net (code "20") (name "/AOUT20") (class "Default")
      (node (ref "SJ20") (pin "2") (pinfunction "2_2") (pintype "passive"))
      (node (ref "SV39") (pin "1") (pinfunction "1_1") (pintype "passive"))
      (node (ref "X2") (pin "30") (pinfunction "S_30") (pintype "passive"))
    )
    (net (code "21") (name "/AOUT21") (class "Default")
      (node (ref "SJ21") (pin "2") (pinfunction "2_2") (pintype "passive"))
      (node (ref "SV41") (pin "1") (pinfunction "1_1") (pintype "passive"))
      (node (ref "X2") (pin "34") (pinfunction "S_34") (pintype "passive"))
    )
    (net (code "22") (name "/AOUT22") (class "Default")
      (node (ref "SJ22") (pin "2") (pinfunction "2_2") (pintype "passive"))
      (node (ref "SV43") (pin "1") (pinfunction "1_1") (pintype "passive"))
      (node (ref "X2") (pin "2") (pinfunction "S_2") (pintype "passive"))
    )
    (net (code "23") (name "/AOUT23") (class "Default")
      (node (ref "SJ23") (pin "2") (pinfunction "2_2") (pintype "passive"))
      (node (ref "SV45") (pin "1") (pinfunction "1_1") (pintype "passive"))
      (node (ref "X2") (pin "10") (pinfunction "S_10") (pintype "passive"))
    )
    (net (code "24") (name "/AOUT24") (class "Default")
      (node (ref "SJ24") (pin "2") (pinfunction "2_2") (pintype "passive"))
      (node (ref "SV47") (pin "1") (pinfunction "1_1") (pintype "passive"))
      (node (ref "X2") (pin "17") (pinfunction "S_17") (pintype "passive"))
    )
    (net (code "25") (name "/AOUT25") (class "Default")
      (node (ref "SJ25") (pin "2") (pinfunction "2_2") (pintype "passive"))
      (node (ref "SV49") (pin "1") (pinfunction "1_1") (pintype "passive"))
      (node (ref "X2") (pin "21") (pinfunction "S_21") (pintype "passive"))
    )
    (net (code "26") (name "/AOUT26") (class "Default")
      (node (ref "SJ26") (pin "2") (pinfunction "2_2") (pintype "passive"))
      (node (ref "SV51") (pin "1") (pinfunction "1_1") (pintype "passive"))
      (node (ref "X2") (pin "25") (pinfunction "S_25") (pintype "passive"))
    )
    (net (code "27") (name "/AOUT27") (class "Default")
      (node (ref "SJ27") (pin "2") (pinfunction "2_2") (pintype "passive"))
      (node (ref "SV53") (pin "1") (pinfunction "1_1") (pintype "passive"))
      (node (ref "X2") (pin "29") (pinfunction "S_29") (pintype "passive"))
    )
    (net (code "28") (name "/AOUT28") (class "Default")
      (node (ref "SJ28") (pin "2") (pinfunction "2_2") (pintype "passive"))
      (node (ref "SV55") (pin "1") (pinfunction "1_1") (pintype "passive"))
      (node (ref "X2") (pin "33") (pinfunction "S_33") (pintype "passive"))
    )
    (net (code "29") (name "/GAIN1") (class "Default")
      (node (ref "SJ1") (pin "1") (pinfunction "1_1") (pintype "passive"))
      (node (ref "SV2") (pin "4") (pinfunction "4_4") (pintype "passive"))
    )
    (net (code "30") (name "/GAIN2") (class "Default")
      (node (ref "SJ2") (pin "1") (pinfunction "1_1") (pintype "passive"))
      (node (ref "SV4") (pin "4") (pinfunction "4_4") (pintype "passive"))
    )
    (net (code "31") (name "/GAIN3") (class "Default")
      (node (ref "SJ3") (pin "1") (pinfunction "1_1") (pintype "passive"))
      (node (ref "SV6") (pin "4") (pinfunction "4_4") (pintype "passive"))
    )
    (net (code "32") (name "/GAIN4") (class "Default")
      (node (ref "SJ4") (pin "1") (pinfunction "1_1") (pintype "passive"))
      (node (ref "SV8") (pin "4") (pinfunction "4_4") (pintype "passive"))
    )
    (net (code "33") (name "/GAIN5") (class "Default")
      (node (ref "SJ5") (pin "1") (pinfunction "1_1") (pintype "passive"))
      (node (ref "SV10") (pin "4") (pinfunction "4_4") (pintype "passive"))
    )
    (net (code "34") (name "/GAIN6") (class "Default")
      (node (ref "SJ6") (pin "1") (pinfunction "1_1") (pintype "passive"))
      (node (ref "SV12") (pin "4") (pinfunction "4_4") (pintype "passive"))
    )
    (net (code "35") (name "/GAIN7") (class "Default")
      (node (ref "SJ7") (pin "1") (pinfunction "1_1") (pintype "passive"))
      (node (ref "SV14") (pin "4") (pinfunction "4_4") (pintype "passive"))
    )
    (net (code "36") (name "/GAIN8") (class "Default")
      (node (ref "SJ8") (pin "1") (pinfunction "1_1") (pintype "passive"))
      (node (ref "SV16") (pin "4") (pinfunction "4_4") (pintype "passive"))
    )
    (net (code "37") (name "/GAIN9") (class "Default")
      (node (ref "SJ9") (pin "1") (pinfunction "1_1") (pintype "passive"))
      (node (ref "SV18") (pin "4") (pinfunction "4_4") (pintype "passive"))
    )
    (net (code "38") (name "/GAIN10") (class "Default")
      (node (ref "SJ10") (pin "1") (pinfunction "1_1") (pintype "passive"))
      (node (ref "SV20") (pin "4") (pinfunction "4_4") (pintype "passive"))
    )
    (net (code "39") (name "/GAIN11") (class "Default")
      (node (ref "SJ11") (pin "1") (pinfunction "1_1") (pintype "passive"))
      (node (ref "SV22") (pin "4") (pinfunction "4_4") (pintype "passive"))
    )
    (net (code "40") (name "/GAIN12") (class "Default")
      (node (ref "SJ12") (pin "1") (pinfunction "1_1") (pintype "passive"))
      (node (ref "SV24") (pin "4") (pinfunction "4_4") (pintype "passive"))
    )
    (net (code "41") (name "/GAIN13") (class "Default")
      (node (ref "SJ13") (pin "1") (pinfunction "1_1") (pintype "passive"))
      (node (ref "SV26") (pin "4") (pinfunction "4_4") (pintype "passive"))
    )
    (net (code "42") (name "/GAIN14") (class "Default")
      (node (ref "SJ14") (pin "1") (pinfunction "1_1") (pintype "passive"))
      (node (ref "SV28") (pin "4") (pinfunction "4_4") (pintype "passive"))
    )
    (net (code "43") (name "/GAIN15") (class "Default")
      (node (ref "SJ15") (pin "1") (pinfunction "1_1") (pintype "passive"))
      (node (ref "SV30") (pin "4") (pinfunction "4_4") (pintype "passive"))
    )
    (net (code "44") (name "/GAIN16") (class "Default")
      (node (ref "SJ16") (pin "1") (pinfunction "1_1") (pintype "passive"))
      (node (ref "SV32") (pin "4") (pinfunction "4_4") (pintype "passive"))
    )
    (net (code "45") (name "/GAIN17") (class "Default")
      (node (ref "SJ17") (pin "1") (pinfunction "1_1") (pintype "passive"))
      (node (ref "SV34") (pin "4") (pinfunction "4_4") (pintype "passive"))
    )
    (net (code "46") (name "/GAIN18") (class "Default")
      (node (ref "SJ18") (pin "1") (pinfunction "1_1") (pintype "passive"))
      (node (ref "SV36") (pin "4") (pinfunction "4_4") (pintype "passive"))
    )
    (net (code "47") (name "/GAIN19") (class "Default")
      (node (ref "SJ19") (pin "1") (pinfunction "1_1") (pintype "passive"))
      (node (ref "SV38") (pin "4") (pinfunction "4_4") (pintype "passive"))
    )
    (net (code "48") (name "/GAIN20") (class "Default")
      (node (ref "SJ20") (pin "1") (pinfunction "1_1") (pintype "passive"))
      (node (ref "SV40") (pin "4") (pinfunction "4_4") (pintype "passive"))
    )
    (net (code "49") (name "/GAIN21") (class "Default")
      (node (ref "SJ21") (pin "1") (pinfunction "1_1") (pintype "passive"))
      (node (ref "SV42") (pin "4") (pinfunction "4_4") (pintype "passive"))
    )
    (net (code "50") (name "/GAIN22") (class "Default")
      (node (ref "SJ22") (pin "1") (pinfunction "1_1") (pintype "passive"))
      (node (ref "SV44") (pin "4") (pinfunction "4_4") (pintype "passive"))
    )
    (net (code "51") (name "/GAIN23") (class "Default")
      (node (ref "SJ23") (pin "1") (pinfunction "1_1") (pintype "passive"))
      (node (ref "SV46") (pin "4") (pinfunction "4_4") (pintype "passive"))
    )
    (net (code "52") (name "/GAIN24") (class "Default")
      (node (ref "SJ24") (pin "1") (pinfunction "1_1") (pintype "passive"))
      (node (ref "SV48") (pin "4") (pinfunction "4_4") (pintype "passive"))
    )
    (net (code "53") (name "/GAIN25") (class "Default")
      (node (ref "SJ25") (pin "1") (pinfunction "1_1") (pintype "passive"))
      (node (ref "SV50") (pin "4") (pinfunction "4_4") (pintype "passive"))
    )
    (net (code "54") (name "/GAIN26") (class "Default")
      (node (ref "SJ26") (pin "1") (pinfunction "1_1") (pintype "passive"))
      (node (ref "SV52") (pin "4") (pinfunction "4_4") (pintype "passive"))
    )
    (net (code "55") (name "/GAIN27") (class "Default")
      (node (ref "SJ27") (pin "1") (pinfunction "1_1") (pintype "passive"))
      (node (ref "SV54") (pin "4") (pinfunction "4_4") (pintype "passive"))
    )
    (net (code "56") (name "/GAIN28") (class "Default")
      (node (ref "SJ28") (pin "1") (pinfunction "1_1") (pintype "passive"))
      (node (ref "SV56") (pin "4") (pinfunction "4_4") (pintype "passive"))
    )
    (net (code "57") (name "/GND_ANA") (class "Default")
      (node (ref "SV1") (pin "4") (pinfunction "4_4") (pintype "passive"))
      (node (ref "SV10") (pin "3") (pinfunction "3_3") (pintype "passive"))
      (node (ref "SV11") (pin "4") (pinfunction "4_4") (pintype "passive"))
      (node (ref "SV12") (pin "3") (pinfunction "3_3") (pintype "passive"))
      (node (ref "SV13") (pin "4") (pinfunction "4_4") (pintype "passive"))
      (node (ref "SV14") (pin "3") (pinfunction "3_3") (pintype "passive"))
      (node (ref "SV15") (pin "4") (pinfunction "4_4") (pintype "passive"))
      (node (ref "SV16") (pin "3") (pinfunction "3_3") (pintype "passive"))
      (node (ref "SV17") (pin "4") (pinfunction "4_4") (pintype "passive"))
      (node (ref "SV18") (pin "3") (pinfunction "3_3") (pintype "passive"))
      (node (ref "SV19") (pin "4") (pinfunction "4_4") (pintype "passive"))
      (node (ref "SV2") (pin "3") (pinfunction "3_3") (pintype "passive"))
      (node (ref "SV20") (pin "3") (pinfunction "3_3") (pintype "passive"))
      (node (ref "SV21") (pin "4") (pinfunction "4_4") (pintype "passive"))
      (node (ref "SV22") (pin "3") (pinfunction "3_3") (pintype "passive"))
      (node (ref "SV23") (pin "4") (pinfunction "4_4") (pintype "passive"))
      (node (ref "SV24") (pin "3") (pinfunction "3_3") (pintype "passive"))
      (node (ref "SV25") (pin "4") (pinfunction "4_4") (pintype "passive"))
      (node (ref "SV26") (pin "3") (pinfunction "3_3") (pintype "passive"))
      (node (ref "SV27") (pin "4") (pinfunction "4_4") (pintype "passive"))
      (node (ref "SV28") (pin "3") (pinfunction "3_3") (pintype "passive"))
      (node (ref "SV29") (pin "4") (pinfunction "4_4") (pintype "passive"))
      (node (ref "SV3") (pin "4") (pinfunction "4_4") (pintype "passive"))
      (node (ref "SV30") (pin "3") (pinfunction "3_3") (pintype "passive"))
      (node (ref "SV31") (pin "4") (pinfunction "4_4") (pintype "passive"))
      (node (ref "SV32") (pin "3") (pinfunction "3_3") (pintype "passive"))
      (node (ref "SV33") (pin "4") (pinfunction "4_4") (pintype "passive"))
      (node (ref "SV34") (pin "3") (pinfunction "3_3") (pintype "passive"))
      (node (ref "SV35") (pin "4") (pinfunction "4_4") (pintype "passive"))
      (node (ref "SV36") (pin "3") (pinfunction "3_3") (pintype "passive"))
      (node (ref "SV37") (pin "4") (pinfunction "4_4") (pintype "passive"))
      (node (ref "SV38") (pin "3") (pinfunction "3_3") (pintype "passive"))
      (node (ref "SV39") (pin "4") (pinfunction "4_4") (pintype "passive"))
      (node (ref "SV4") (pin "3") (pinfunction "3_3") (pintype "passive"))
      (node (ref "SV40") (pin "3") (pinfunction "3_3") (pintype "passive"))
      (node (ref "SV41") (pin "4") (pinfunction "4_4") (pintype "passive"))
      (node (ref "SV42") (pin "3") (pinfunction "3_3") (pintype "passive"))
      (node (ref "SV43") (pin "4") (pinfunction "4_4") (pintype "passive"))
      (node (ref "SV44") (pin "3") (pinfunction "3_3") (pintype "passive"))
      (node (ref "SV45") (pin "4") (pinfunction "4_4") (pintype "passive"))
      (node (ref "SV46") (pin "3") (pinfunction "3_3") (pintype "passive"))
      (node (ref "SV47") (pin "4") (pinfunction "4_4") (pintype "passive"))
      (node (ref "SV48") (pin "3") (pinfunction "3_3") (pintype "passive"))
      (node (ref "SV49") (pin "4") (pinfunction "4_4") (pintype "passive"))
      (node (ref "SV5") (pin "4") (pinfunction "4_4") (pintype "passive"))
      (node (ref "SV50") (pin "3") (pinfunction "3_3") (pintype "passive"))
      (node (ref "SV51") (pin "4") (pinfunction "4_4") (pintype "passive"))
      (node (ref "SV52") (pin "3") (pinfunction "3_3") (pintype "passive"))
      (node (ref "SV53") (pin "4") (pinfunction "4_4") (pintype "passive"))
      (node (ref "SV54") (pin "3") (pinfunction "3_3") (pintype "passive"))
      (node (ref "SV55") (pin "4") (pinfunction "4_4") (pintype "passive"))
      (node (ref "SV56") (pin "3") (pinfunction "3_3") (pintype "passive"))
      (node (ref "SV6") (pin "3") (pinfunction "3_3") (pintype "passive"))
      (node (ref "SV7") (pin "4") (pinfunction "4_4") (pintype "passive"))
      (node (ref "SV8") (pin "3") (pinfunction "3_3") (pintype "passive"))
      (node (ref "SV9") (pin "4") (pinfunction "4_4") (pintype "passive"))
      (node (ref "X2") (pin "11") (pinfunction "S_11") (pintype "passive"))
      (node (ref "X2") (pin "13") (pinfunction "S_13") (pintype "passive"))
      (node (ref "X2") (pin "15") (pinfunction "S_15") (pintype "passive"))
      (node (ref "X2") (pin "9") (pinfunction "S_9") (pintype "passive"))
    )
    (net (code "58") (name "/GND_DIG") (class "Default")
      (node (ref "D1") (pin "C") (pinfunction "C_C") (pintype "passive"))
      (node (ref "D10") (pin "C") (pinfunction "C_C") (pintype "passive"))
      (node (ref "D11") (pin "C") (pinfunction "C_C") (pintype "passive"))
      (node (ref "D12") (pin "C") (pinfunction "C_C") (pintype "passive"))
      (node (ref "D13") (pin "C") (pinfunction "C_C") (pintype "passive"))
      (node (ref "D14") (pin "C") (pinfunction "C_C") (pintype "passive"))
      (node (ref "D15") (pin "C") (pinfunction "C_C") (pintype "passive"))
      (node (ref "D16") (pin "C") (pinfunction "C_C") (pintype "passive"))
      (node (ref "D17") (pin "C") (pinfunction "C_C") (pintype "passive"))
      (node (ref "D18") (pin "C") (pinfunction "C_C") (pintype "passive"))
      (node (ref "D19") (pin "C") (pinfunction "C_C") (pintype "passive"))
      (node (ref "D2") (pin "C") (pinfunction "C_C") (pintype "passive"))
      (node (ref "D20") (pin "C") (pinfunction "C_C") (pintype "passive"))
      (node (ref "D21") (pin "C") (pinfunction "C_C") (pintype "passive"))
      (node (ref "D22") (pin "C") (pinfunction "C_C") (pintype "passive"))
      (node (ref "D23") (pin "C") (pinfunction "C_C") (pintype "passive"))
      (node (ref "D24") (pin "C") (pinfunction "C_C") (pintype "passive"))
      (node (ref "D25") (pin "C") (pinfunction "C_C") (pintype "passive"))
      (node (ref "D26") (pin "C") (pinfunction "C_C") (pintype "passive"))
      (node (ref "D27") (pin "C") (pinfunction "C_C") (pintype "passive"))
      (node (ref "D28") (pin "C") (pinfunction "C_C") (pintype "passive"))
      (node (ref "D29") (pin "C") (pinfunction "C_C") (pintype "passive"))
      (node (ref "D3") (pin "C") (pinfunction "C_C") (pintype "passive"))
      (node (ref "D30") (pin "C") (pinfunction "C_C") (pintype "passive"))
      (node (ref "D31") (pin "C") (pinfunction "C_C") (pintype "passive"))
      (node (ref "D32") (pin "C") (pinfunction "C_C") (pintype "passive"))
      (node (ref "D33") (pin "C") (pinfunction "C_C") (pintype "passive"))
      (node (ref "D34") (pin "C") (pinfunction "C_C") (pintype "passive"))
      (node (ref "D35") (pin "C") (pinfunction "C_C") (pintype "passive"))
      (node (ref "D36") (pin "C") (pinfunction "C_C") (pintype "passive"))
      (node (ref "D37") (pin "C") (pinfunction "C_C") (pintype "passive"))
      (node (ref "D38") (pin "C") (pinfunction "C_C") (pintype "passive"))
      (node (ref "D39") (pin "C") (pinfunction "C_C") (pintype "passive"))
      (node (ref "D4") (pin "C") (pinfunction "C_C") (pintype "passive"))
      (node (ref "D40") (pin "C") (pinfunction "C_C") (pintype "passive"))
      (node (ref "D41") (pin "C") (pinfunction "C_C") (pintype "passive"))
      (node (ref "D42") (pin "C") (pinfunction "C_C") (pintype "passive"))
      (node (ref "D43") (pin "C") (pinfunction "C_C") (pintype "passive"))
      (node (ref "D44") (pin "C") (pinfunction "C_C") (pintype "passive"))
      (node (ref "D45") (pin "C") (pinfunction "C_C") (pintype "passive"))
      (node (ref "D46") (pin "C") (pinfunction "C_C") (pintype "passive"))
      (node (ref "D47") (pin "C") (pinfunction "C_C") (pintype "passive"))
      (node (ref "D48") (pin "C") (pinfunction "C_C") (pintype "passive"))
      (node (ref "D5") (pin "C") (pinfunction "C_C") (pintype "passive"))
      (node (ref "D6") (pin "C") (pinfunction "C_C") (pintype "passive"))
      (node (ref "D7") (pin "C") (pinfunction "C_C") (pintype "passive"))
      (node (ref "D8") (pin "C") (pinfunction "C_C") (pintype "passive"))
      (node (ref "D9") (pin "C") (pinfunction "C_C") (pintype "passive"))
      (node (ref "X1") (pin "49") (pinfunction "S_49") (pintype "passive"))
      (node (ref "X1") (pin "50") (pinfunction "S_50") (pintype "passive"))
    )
    (net (code "59") (name "/VDD_ANA") (class "Default")
      (node (ref "SV10") (pin "1") (pinfunction "1_1") (pintype "passive"))
      (node (ref "SV12") (pin "1") (pinfunction "1_1") (pintype "passive"))
      (node (ref "SV14") (pin "1") (pinfunction "1_1") (pintype "passive"))
      (node (ref "SV16") (pin "1") (pinfunction "1_1") (pintype "passive"))
      (node (ref "SV18") (pin "1") (pinfunction "1_1") (pintype "passive"))
      (node (ref "SV2") (pin "1") (pinfunction "1_1") (pintype "passive"))
      (node (ref "SV20") (pin "1") (pinfunction "1_1") (pintype "passive"))
      (node (ref "SV22") (pin "1") (pinfunction "1_1") (pintype "passive"))
      (node (ref "SV24") (pin "1") (pinfunction "1_1") (pintype "passive"))
      (node (ref "SV26") (pin "1") (pinfunction "1_1") (pintype "passive"))
      (node (ref "SV28") (pin "1") (pinfunction "1_1") (pintype "passive"))
      (node (ref "SV30") (pin "1") (pinfunction "1_1") (pintype "passive"))
      (node (ref "SV32") (pin "1") (pinfunction "1_1") (pintype "passive"))
      (node (ref "SV34") (pin "1") (pinfunction "1_1") (pintype "passive"))
      (node (ref "SV36") (pin "1") (pinfunction "1_1") (pintype "passive"))
      (node (ref "SV38") (pin "1") (pinfunction "1_1") (pintype "passive"))
      (node (ref "SV4") (pin "1") (pinfunction "1_1") (pintype "passive"))
      (node (ref "SV40") (pin "1") (pinfunction "1_1") (pintype "passive"))
      (node (ref "SV42") (pin "1") (pinfunction "1_1") (pintype "passive"))
      (node (ref "SV44") (pin "1") (pinfunction "1_1") (pintype "passive"))
      (node (ref "SV46") (pin "1") (pinfunction "1_1") (pintype "passive"))
      (node (ref "SV48") (pin "1") (pinfunction "1_1") (pintype "passive"))
      (node (ref "SV50") (pin "1") (pinfunction "1_1") (pintype "passive"))
      (node (ref "SV52") (pin "1") (pinfunction "1_1") (pintype "passive"))
      (node (ref "SV54") (pin "1") (pinfunction "1_1") (pintype "passive"))
      (node (ref "SV56") (pin "1") (pinfunction "1_1") (pintype "passive"))
      (node (ref "SV6") (pin "1") (pinfunction "1_1") (pintype "passive"))
      (node (ref "SV8") (pin "1") (pinfunction "1_1") (pintype "passive"))
      (node (ref "X2") (pin "1") (pinfunction "S_1") (pintype "passive"))
      (node (ref "X2") (pin "3") (pinfunction "S_3") (pintype "passive"))
      (node (ref "X2") (pin "5") (pinfunction "S_5") (pintype "passive"))
      (node (ref "X2") (pin "7") (pinfunction "S_7") (pintype "passive"))
    )
    (net (code "60") (name "/VLED1") (class "Default")
      (node (ref "D1") (pin "A") (pinfunction "A_A") (pintype "passive"))
      (node (ref "X1") (pin "1") (pinfunction "S_1") (pintype "passive"))
    )
    (net (code "61") (name "/VLED2") (class "Default")
      (node (ref "D2") (pin "A") (pinfunction "A_A") (pintype "passive"))
      (node (ref "X1") (pin "2") (pinfunction "S_2") (pintype "passive"))
    )
    (net (code "62") (name "/VLED3") (class "Default")
      (node (ref "D3") (pin "A") (pinfunction "A_A") (pintype "passive"))
      (node (ref "X1") (pin "7") (pinfunction "S_7") (pintype "passive"))
    )
    (net (code "63") (name "/VLED4") (class "Default")
      (node (ref "D4") (pin "A") (pinfunction "A_A") (pintype "passive"))
      (node (ref "X1") (pin "8") (pinfunction "S_8") (pintype "passive"))
    )
    (net (code "64") (name "/VLED5") (class "Default")
      (node (ref "D5") (pin "A") (pinfunction "A_A") (pintype "passive"))
      (node (ref "X1") (pin "13") (pinfunction "S_13") (pintype "passive"))
    )
    (net (code "65") (name "/VLED6") (class "Default")
      (node (ref "D6") (pin "A") (pinfunction "A_A") (pintype "passive"))
      (node (ref "X1") (pin "14") (pinfunction "S_14") (pintype "passive"))
    )
    (net (code "66") (name "/VLED7") (class "Default")
      (node (ref "D7") (pin "A") (pinfunction "A_A") (pintype "passive"))
      (node (ref "X1") (pin "19") (pinfunction "S_19") (pintype "passive"))
    )
    (net (code "67") (name "/VLED8") (class "Default")
      (node (ref "D8") (pin "A") (pinfunction "A_A") (pintype "passive"))
      (node (ref "X1") (pin "20") (pinfunction "S_20") (pintype "passive"))
    )
    (net (code "68") (name "/VLED9") (class "Default")
      (node (ref "D9") (pin "A") (pinfunction "A_A") (pintype "passive"))
      (node (ref "X1") (pin "25") (pinfunction "S_25") (pintype "passive"))
    )
    (net (code "69") (name "/VLED10") (class "Default")
      (node (ref "D10") (pin "A") (pinfunction "A_A") (pintype "passive"))
      (node (ref "X1") (pin "26") (pinfunction "S_26") (pintype "passive"))
    )
    (net (code "70") (name "/VLED11") (class "Default")
      (node (ref "D11") (pin "A") (pinfunction "A_A") (pintype "passive"))
      (node (ref "X1") (pin "31") (pinfunction "S_31") (pintype "passive"))
    )
    (net (code "71") (name "/VLED12") (class "Default")
      (node (ref "D12") (pin "A") (pinfunction "A_A") (pintype "passive"))
      (node (ref "X1") (pin "32") (pinfunction "S_32") (pintype "passive"))
    )
    (net (code "72") (name "/VLED13") (class "Default")
      (node (ref "D13") (pin "A") (pinfunction "A_A") (pintype "passive"))
      (node (ref "X1") (pin "37") (pinfunction "S_37") (pintype "passive"))
    )
    (net (code "73") (name "/VLED14") (class "Default")
      (node (ref "D14") (pin "A") (pinfunction "A_A") (pintype "passive"))
      (node (ref "X1") (pin "38") (pinfunction "S_38") (pintype "passive"))
    )
    (net (code "74") (name "/VLED15") (class "Default")
      (node (ref "D15") (pin "A") (pinfunction "A_A") (pintype "passive"))
      (node (ref "X1") (pin "43") (pinfunction "S_43") (pintype "passive"))
    )
    (net (code "75") (name "/VLED16") (class "Default")
      (node (ref "D16") (pin "A") (pinfunction "A_A") (pintype "passive"))
      (node (ref "X1") (pin "44") (pinfunction "S_44") (pintype "passive"))
    )
    (net (code "76") (name "/VLED17") (class "Default")
      (node (ref "D17") (pin "A") (pinfunction "A_A") (pintype "passive"))
      (node (ref "X1") (pin "3") (pinfunction "S_3") (pintype "passive"))
    )
    (net (code "77") (name "/VLED18") (class "Default")
      (node (ref "D18") (pin "A") (pinfunction "A_A") (pintype "passive"))
      (node (ref "X1") (pin "4") (pinfunction "S_4") (pintype "passive"))
    )
    (net (code "78") (name "/VLED19") (class "Default")
      (node (ref "D19") (pin "A") (pinfunction "A_A") (pintype "passive"))
      (node (ref "X1") (pin "9") (pinfunction "S_9") (pintype "passive"))
    )
    (net (code "79") (name "/VLED20") (class "Default")
      (node (ref "D20") (pin "A") (pinfunction "A_A") (pintype "passive"))
      (node (ref "X1") (pin "10") (pinfunction "S_10") (pintype "passive"))
    )
    (net (code "80") (name "/VLED21") (class "Default")
      (node (ref "D21") (pin "A") (pinfunction "A_A") (pintype "passive"))
      (node (ref "X1") (pin "15") (pinfunction "S_15") (pintype "passive"))
    )
    (net (code "81") (name "/VLED22") (class "Default")
      (node (ref "D22") (pin "A") (pinfunction "A_A") (pintype "passive"))
      (node (ref "X1") (pin "16") (pinfunction "S_16") (pintype "passive"))
    )
    (net (code "82") (name "/VLED23") (class "Default")
      (node (ref "D23") (pin "A") (pinfunction "A_A") (pintype "passive"))
      (node (ref "X1") (pin "21") (pinfunction "S_21") (pintype "passive"))
    )
    (net (code "83") (name "/VLED24") (class "Default")
      (node (ref "D24") (pin "A") (pinfunction "A_A") (pintype "passive"))
      (node (ref "X1") (pin "22") (pinfunction "S_22") (pintype "passive"))
    )
    (net (code "84") (name "/VLED25") (class "Default")
      (node (ref "D25") (pin "A") (pinfunction "A_A") (pintype "passive"))
      (node (ref "X1") (pin "27") (pinfunction "S_27") (pintype "passive"))
    )
    (net (code "85") (name "/VLED26") (class "Default")
      (node (ref "D26") (pin "A") (pinfunction "A_A") (pintype "passive"))
      (node (ref "X1") (pin "28") (pinfunction "S_28") (pintype "passive"))
    )
    (net (code "86") (name "/VLED27") (class "Default")
      (node (ref "D27") (pin "A") (pinfunction "A_A") (pintype "passive"))
      (node (ref "X1") (pin "33") (pinfunction "S_33") (pintype "passive"))
    )
    (net (code "87") (name "/VLED28") (class "Default")
      (node (ref "D28") (pin "A") (pinfunction "A_A") (pintype "passive"))
      (node (ref "X1") (pin "34") (pinfunction "S_34") (pintype "passive"))
    )
    (net (code "88") (name "/VLED29") (class "Default")
      (node (ref "D29") (pin "A") (pinfunction "A_A") (pintype "passive"))
      (node (ref "X1") (pin "39") (pinfunction "S_39") (pintype "passive"))
    )
    (net (code "89") (name "/VLED30") (class "Default")
      (node (ref "D30") (pin "A") (pinfunction "A_A") (pintype "passive"))
      (node (ref "X1") (pin "40") (pinfunction "S_40") (pintype "passive"))
    )
    (net (code "90") (name "/VLED31") (class "Default")
      (node (ref "D31") (pin "A") (pinfunction "A_A") (pintype "passive"))
      (node (ref "X1") (pin "45") (pinfunction "S_45") (pintype "passive"))
    )
    (net (code "91") (name "/VLED32") (class "Default")
      (node (ref "D32") (pin "A") (pinfunction "A_A") (pintype "passive"))
      (node (ref "X1") (pin "46") (pinfunction "S_46") (pintype "passive"))
    )
    (net (code "92") (name "/VLED33") (class "Default")
      (node (ref "D33") (pin "A") (pinfunction "A_A") (pintype "passive"))
      (node (ref "X1") (pin "5") (pinfunction "S_5") (pintype "passive"))
    )
    (net (code "93") (name "/VLED34") (class "Default")
      (node (ref "D34") (pin "A") (pinfunction "A_A") (pintype "passive"))
      (node (ref "X1") (pin "6") (pinfunction "S_6") (pintype "passive"))
    )
    (net (code "94") (name "/VLED35") (class "Default")
      (node (ref "D35") (pin "A") (pinfunction "A_A") (pintype "passive"))
      (node (ref "X1") (pin "11") (pinfunction "S_11") (pintype "passive"))
    )
    (net (code "95") (name "/VLED36") (class "Default")
      (node (ref "D36") (pin "A") (pinfunction "A_A") (pintype "passive"))
      (node (ref "X1") (pin "12") (pinfunction "S_12") (pintype "passive"))
    )
    (net (code "96") (name "/VLED37") (class "Default")
      (node (ref "D37") (pin "A") (pinfunction "A_A") (pintype "passive"))
      (node (ref "X1") (pin "17") (pinfunction "S_17") (pintype "passive"))
    )
    (net (code "97") (name "/VLED38") (class "Default")
      (node (ref "D38") (pin "A") (pinfunction "A_A") (pintype "passive"))
      (node (ref "X1") (pin "18") (pinfunction "S_18") (pintype "passive"))
    )
    (net (code "98") (name "/VLED39") (class "Default")
      (node (ref "D39") (pin "A") (pinfunction "A_A") (pintype "passive"))
      (node (ref "X1") (pin "23") (pinfunction "S_23") (pintype "passive"))
    )
    (net (code "99") (name "/VLED40") (class "Default")
      (node (ref "D40") (pin "A") (pinfunction "A_A") (pintype "passive"))
      (node (ref "X1") (pin "24") (pinfunction "S_24") (pintype "passive"))
    )
    (net (code "100") (name "/VLED41") (class "Default")
      (node (ref "D41") (pin "A") (pinfunction "A_A") (pintype "passive"))
      (node (ref "X1") (pin "29") (pinfunction "S_29") (pintype "passive"))
    )
    (net (code "101") (name "/VLED42") (class "Default")
      (node (ref "D42") (pin "A") (pinfunction "A_A") (pintype "passive"))
      (node (ref "X1") (pin "30") (pinfunction "S_30") (pintype "passive"))
    )
    (net (code "102") (name "/VLED43") (class "Default")
      (node (ref "D43") (pin "A") (pinfunction "A_A") (pintype "passive"))
      (node (ref "X1") (pin "35") (pinfunction "S_35") (pintype "passive"))
    )
    (net (code "103") (name "/VLED44") (class "Default")
      (node (ref "D44") (pin "A") (pinfunction "A_A") (pintype "passive"))
      (node (ref "X1") (pin "36") (pinfunction "S_36") (pintype "passive"))
    )
    (net (code "104") (name "/VLED45") (class "Default")
      (node (ref "D45") (pin "A") (pinfunction "A_A") (pintype "passive"))
      (node (ref "X1") (pin "41") (pinfunction "S_41") (pintype "passive"))
    )
    (net (code "105") (name "/VLED46") (class "Default")
      (node (ref "D46") (pin "A") (pinfunction "A_A") (pintype "passive"))
      (node (ref "X1") (pin "42") (pinfunction "S_42") (pintype "passive"))
    )
    (net (code "106") (name "/VLED47") (class "Default")
      (node (ref "D47") (pin "A") (pinfunction "A_A") (pintype "passive"))
      (node (ref "X1") (pin "47") (pinfunction "S_47") (pintype "passive"))
    )
    (net (code "107") (name "/VLED48") (class "Default")
      (node (ref "D48") (pin "A") (pinfunction "A_A") (pintype "passive"))
      (node (ref "X1") (pin "48") (pinfunction "S_48") (pintype "passive"))
    )
    (net (code "108") (name "unconnected-(SV1-Pad2)") (class "Default")
      (node (ref "SV1") (pin "2") (pinfunction "2_2") (pintype "passive"))
    )
    (net (code "109") (name "unconnected-(SV1-Pad3)") (class "Default")
      (node (ref "SV1") (pin "3") (pinfunction "3_3") (pintype "passive"))
    )
    (net (code "110") (name "unconnected-(SV2-Pad2)") (class "Default")
      (node (ref "SV2") (pin "2") (pinfunction "2_2") (pintype "passive"))
    )
    (net (code "111") (name "unconnected-(SV3-Pad2)") (class "Default")
      (node (ref "SV3") (pin "2") (pinfunction "2_2") (pintype "passive"))
    )
    (net (code "112") (name "unconnected-(SV3-Pad3)") (class "Default")
      (node (ref "SV3") (pin "3") (pinfunction "3_3") (pintype "passive"))
    )
    (net (code "113") (name "unconnected-(SV4-Pad2)") (class "Default")
      (node (ref "SV4") (pin "2") (pinfunction "2_2") (pintype "passive"))
    )
    (net (code "114") (name "unconnected-(SV5-Pad2)") (class "Default")
      (node (ref "SV5") (pin "2") (pinfunction "2_2") (pintype "passive"))
    )
    (net (code "115") (name "unconnected-(SV5-Pad3)") (class "Default")
      (node (ref "SV5") (pin "3") (pinfunction "3_3") (pintype "passive"))
    )
    (net (code "116") (name "unconnected-(SV6-Pad2)") (class "Default")
      (node (ref "SV6") (pin "2") (pinfunction "2_2") (pintype "passive"))
    )
    (net (code "117") (name "unconnected-(SV7-Pad2)") (class "Default")
      (node (ref "SV7") (pin "2") (pinfunction "2_2") (pintype "passive"))
    )
    (net (code "118") (name "unconnected-(SV7-Pad3)") (class "Default")
      (node (ref "SV7") (pin "3") (pinfunction "3_3") (pintype "passive"))
    )
    (net (code "119") (name "unconnected-(SV8-Pad2)") (class "Default")
      (node (ref "SV8") (pin "2") (pinfunction "2_2") (pintype "passive"))
    )
    (net (code "120") (name "unconnected-(SV9-Pad2)") (class "Default")
      (node (ref "SV9") (pin "2") (pinfunction "2_2") (pintype "passive"))
    )
    (net (code "121") (name "unconnected-(SV9-Pad3)") (class "Default")
      (node (ref "SV9") (pin "3") (pinfunction "3_3") (pintype "passive"))
    )
    (net (code "122") (name "unconnected-(SV10-Pad2)") (class "Default")
      (node (ref "SV10") (pin "2") (pinfunction "2_2") (pintype "passive"))
    )
    (net (code "123") (name "unconnected-(SV11-Pad2)") (class "Default")
      (node (ref "SV11") (pin "2") (pinfunction "2_2") (pintype "passive"))
    )
    (net (code "124") (name "unconnected-(SV11-Pad3)") (class "Default")
      (node (ref "SV11") (pin "3") (pinfunction "3_3") (pintype "passive"))
    )
    (net (code "125") (name "unconnected-(SV12-Pad2)") (class "Default")
      (node (ref "SV12") (pin "2") (pinfunction "2_2") (pintype "passive"))
    )
    (net (code "126") (name "unconnected-(SV13-Pad2)") (class "Default")
      (node (ref "SV13") (pin "2") (pinfunction "2_2") (pintype "passive"))
    )
    (net (code "127") (name "unconnected-(SV13-Pad3)") (class "Default")
      (node (ref "SV13") (pin "3") (pinfunction "3_3") (pintype "passive"))
    )
    (net (code "128") (name "unconnected-(SV14-Pad2)") (class "Default")
      (node (ref "SV14") (pin "2") (pinfunction "2_2") (pintype "passive"))
    )
    (net (code "129") (name "unconnected-(SV15-Pad2)") (class "Default")
      (node (ref "SV15") (pin "2") (pinfunction "2_2") (pintype "passive"))
    )
    (net (code "130") (name "unconnected-(SV15-Pad3)") (class "Default")
      (node (ref "SV15") (pin "3") (pinfunction "3_3") (pintype "passive"))
    )
    (net (code "131") (name "unconnected-(SV16-Pad2)") (class "Default")
      (node (ref "SV16") (pin "2") (pinfunction "2_2") (pintype "passive"))
    )
    (net (code "132") (name "unconnected-(SV17-Pad2)") (class "Default")
      (node (ref "SV17") (pin "2") (pinfunction "2_2") (pintype "passive"))
    )
    (net (code "133") (name "unconnected-(SV17-Pad3)") (class "Default")
      (node (ref "SV17") (pin "3") (pinfunction "3_3") (pintype "passive"))
    )
    (net (code "134") (name "unconnected-(SV18-Pad2)") (class "Default")
      (node (ref "SV18") (pin "2") (pinfunction "2_2") (pintype "passive"))
    )
    (net (code "135") (name "unconnected-(SV19-Pad2)") (class "Default")
      (node (ref "SV19") (pin "2") (pinfunction "2_2") (pintype "passive"))
    )
    (net (code "136") (name "unconnected-(SV19-Pad3)") (class "Default")
      (node (ref "SV19") (pin "3") (pinfunction "3_3") (pintype "passive"))
    )
    (net (code "137") (name "unconnected-(SV20-Pad2)") (class "Default")
      (node (ref "SV20") (pin "2") (pinfunction "2_2") (pintype "passive"))
    )
    (net (code "138") (name "unconnected-(SV21-Pad2)") (class "Default")
      (node (ref "SV21") (pin "2") (pinfunction "2_2") (pintype "passive"))
    )
    (net (code "139") (name "unconnected-(SV21-Pad3)") (class "Default")
      (node (ref "SV21") (pin "3") (pinfunction "3_3") (pintype "passive"))
    )
    (net (code "140") (name "unconnected-(SV22-Pad2)") (class "Default")
      (node (ref "SV22") (pin "2") (pinfunction "2_2") (pintype "passive"))
    )
    (net (code "141") (name "unconnected-(SV23-Pad2)") (class "Default")
      (node (ref "SV23") (pin "2") (pinfunction "2_2") (pintype "passive"))
    )
    (net (code "142") (name "unconnected-(SV23-Pad3)") (class "Default")
      (node (ref "SV23") (pin "3") (pinfunction "3_3") (pintype "passive"))
    )
    (net (code "143") (name "unconnected-(SV24-Pad2)") (class "Default")
      (node (ref "SV24") (pin "2") (pinfunction "2_2") (pintype "passive"))
    )
    (net (code "144") (name "unconnected-(SV25-Pad2)") (class "Default")
      (node (ref "SV25") (pin "2") (pinfunction "2_2") (pintype "passive"))
    )
    (net (code "145") (name "unconnected-(SV25-Pad3)") (class "Default")
      (node (ref "SV25") (pin "3") (pinfunction "3_3") (pintype "passive"))
    )
    (net (code "146") (name "unconnected-(SV26-Pad2)") (class "Default")
      (node (ref "SV26") (pin "2") (pinfunction "2_2") (pintype "passive"))
    )
    (net (code "147") (name "unconnected-(SV27-Pad2)") (class "Default")
      (node (ref "SV27") (pin "2") (pinfunction "2_2") (pintype "passive"))
    )
    (net (code "148") (name "unconnected-(SV27-Pad3)") (class "Default")
      (node (ref "SV27") (pin "3") (pinfunction "3_3") (pintype "passive"))
    )
    (net (code "149") (name "unconnected-(SV28-Pad2)") (class "Default")
      (node (ref "SV28") (pin "2") (pinfunction "2_2") (pintype "passive"))
    )
    (net (code "150") (name "unconnected-(SV29-Pad2)") (class "Default")
      (node (ref "SV29") (pin "2") (pinfunction "2_2") (pintype "passive"))
    )
    (net (code "151") (name "unconnected-(SV29-Pad3)") (class "Default")
      (node (ref "SV29") (pin "3") (pinfunction "3_3") (pintype "passive"))
    )
    (net (code "152") (name "unconnected-(SV30-Pad2)") (class "Default")
      (node (ref "SV30") (pin "2") (pinfunction "2_2") (pintype "passive"))
    )
    (net (code "153") (name "unconnected-(SV31-Pad2)") (class "Default")
      (node (ref "SV31") (pin "2") (pinfunction "2_2") (pintype "passive"))
    )
    (net (code "154") (name "unconnected-(SV31-Pad3)") (class "Default")
      (node (ref "SV31") (pin "3") (pinfunction "3_3") (pintype "passive"))
    )
    (net (code "155") (name "unconnected-(SV32-Pad2)") (class "Default")
      (node (ref "SV32") (pin "2") (pinfunction "2_2") (pintype "passive"))
    )
    (net (code "156") (name "unconnected-(SV33-Pad2)") (class "Default")
      (node (ref "SV33") (pin "2") (pinfunction "2_2") (pintype "passive"))
    )
    (net (code "157") (name "unconnected-(SV33-Pad3)") (class "Default")
      (node (ref "SV33") (pin "3") (pinfunction "3_3") (pintype "passive"))
    )
    (net (code "158") (name "unconnected-(SV34-Pad2)") (class "Default")
      (node (ref "SV34") (pin "2") (pinfunction "2_2") (pintype "passive"))
    )
    (net (code "159") (name "unconnected-(SV35-Pad2)") (class "Default")
      (node (ref "SV35") (pin "2") (pinfunction "2_2") (pintype "passive"))
    )
    (net (code "160") (name "unconnected-(SV35-Pad3)") (class "Default")
      (node (ref "SV35") (pin "3") (pinfunction "3_3") (pintype "passive"))
    )
    (net (code "161") (name "unconnected-(SV36-Pad2)") (class "Default")
      (node (ref "SV36") (pin "2") (pinfunction "2_2") (pintype "passive"))
    )
    (net (code "162") (name "unconnected-(SV37-Pad2)") (class "Default")
      (node (ref "SV37") (pin "2") (pinfunction "2_2") (pintype "passive"))
    )
    (net (code "163") (name "unconnected-(SV37-Pad3)") (class "Default")
      (node (ref "SV37") (pin "3") (pinfunction "3_3") (pintype "passive"))
    )
    (net (code "164") (name "unconnected-(SV38-Pad2)") (class "Default")
      (node (ref "SV38") (pin "2") (pinfunction "2_2") (pintype "passive"))
    )
    (net (code "165") (name "unconnected-(SV39-Pad2)") (class "Default")
      (node (ref "SV39") (pin "2") (pinfunction "2_2") (pintype "passive"))
    )
    (net (code "166") (name "unconnected-(SV39-Pad3)") (class "Default")
      (node (ref "SV39") (pin "3") (pinfunction "3_3") (pintype "passive"))
    )
    (net (code "167") (name "unconnected-(SV40-Pad2)") (class "Default")
      (node (ref "SV40") (pin "2") (pinfunction "2_2") (pintype "passive"))
    )
    (net (code "168") (name "unconnected-(SV41-Pad2)") (class "Default")
      (node (ref "SV41") (pin "2") (pinfunction "2_2") (pintype "passive"))
    )
    (net (code "169") (name "unconnected-(SV41-Pad3)") (class "Default")
      (node (ref "SV41") (pin "3") (pinfunction "3_3") (pintype "passive"))
    )
    (net (code "170") (name "unconnected-(SV42-Pad2)") (class "Default")
      (node (ref "SV42") (pin "2") (pinfunction "2_2") (pintype "passive"))
    )
    (net (code "171") (name "unconnected-(SV43-Pad2)") (class "Default")
      (node (ref "SV43") (pin "2") (pinfunction "2_2") (pintype "passive"))
    )
    (net (code "172") (name "unconnected-(SV43-Pad3)") (class "Default")
      (node (ref "SV43") (pin "3") (pinfunction "3_3") (pintype "passive"))
    )
    (net (code "173") (name "unconnected-(SV44-Pad2)") (class "Default")
      (node (ref "SV44") (pin "2") (pinfunction "2_2") (pintype "passive"))
    )
    (net (code "174") (name "unconnected-(SV45-Pad2)") (class "Default")
      (node (ref "SV45") (pin "2") (pinfunction "2_2") (pintype "passive"))
    )
    (net (code "175") (name "unconnected-(SV45-Pad3)") (class "Default")
      (node (ref "SV45") (pin "3") (pinfunction "3_3") (pintype "passive"))
    )
    (net (code "176") (name "unconnected-(SV46-Pad2)") (class "Default")
      (node (ref "SV46") (pin "2") (pinfunction "2_2") (pintype "passive"))
    )
    (net (code "177") (name "unconnected-(SV47-Pad2)") (class "Default")
      (node (ref "SV47") (pin "2") (pinfunction "2_2") (pintype "passive"))
    )
    (net (code "178") (name "unconnected-(SV47-Pad3)") (class "Default")
      (node (ref "SV47") (pin "3") (pinfunction "3_3") (pintype "passive"))
    )
    (net (code "179") (name "unconnected-(SV48-Pad2)") (class "Default")
      (node (ref "SV48") (pin "2") (pinfunction "2_2") (pintype "passive"))
    )
    (net (code "180") (name "unconnected-(SV49-Pad2)") (class "Default")
      (node (ref "SV49") (pin "2") (pinfunction "2_2") (pintype "passive"))
    )
    (net (code "181") (name "unconnected-(SV49-Pad3)") (class "Default")
      (node (ref "SV49") (pin "3") (pinfunction "3_3") (pintype "passive"))
    )
    (net (code "182") (name "unconnected-(SV50-Pad2)") (class "Default")
      (node (ref "SV50") (pin "2") (pinfunction "2_2") (pintype "passive"))
    )
    (net (code "183") (name "unconnected-(SV51-Pad2)") (class "Default")
      (node (ref "SV51") (pin "2") (pinfunction "2_2") (pintype "passive"))
    )
    (net (code "184") (name "unconnected-(SV51-Pad3)") (class "Default")
      (node (ref "SV51") (pin "3") (pinfunction "3_3") (pintype "passive"))
    )
    (net (code "185") (name "unconnected-(SV52-Pad2)") (class "Default")
      (node (ref "SV52") (pin "2") (pinfunction "2_2") (pintype "passive"))
    )
    (net (code "186") (name "unconnected-(SV53-Pad2)") (class "Default")
      (node (ref "SV53") (pin "2") (pinfunction "2_2") (pintype "passive"))
    )
    (net (code "187") (name "unconnected-(SV53-Pad3)") (class "Default")
      (node (ref "SV53") (pin "3") (pinfunction "3_3") (pintype "passive"))
    )
    (net (code "188") (name "unconnected-(SV54-Pad2)") (class "Default")
      (node (ref "SV54") (pin "2") (pinfunction "2_2") (pintype "passive"))
    )
    (net (code "189") (name "unconnected-(SV55-Pad2)") (class "Default")
      (node (ref "SV55") (pin "2") (pinfunction "2_2") (pintype "passive"))
    )
    (net (code "190") (name "unconnected-(SV55-Pad3)") (class "Default")
      (node (ref "SV55") (pin "3") (pinfunction "3_3") (pintype "passive"))
    )
    (net (code "191") (name "unconnected-(SV56-Pad2)") (class "Default")
      (node (ref "SV56") (pin "2") (pinfunction "2_2") (pintype "passive"))
    )
  )
)
